# main.net
KiCad netlist of a schematic drawn in EAGLE
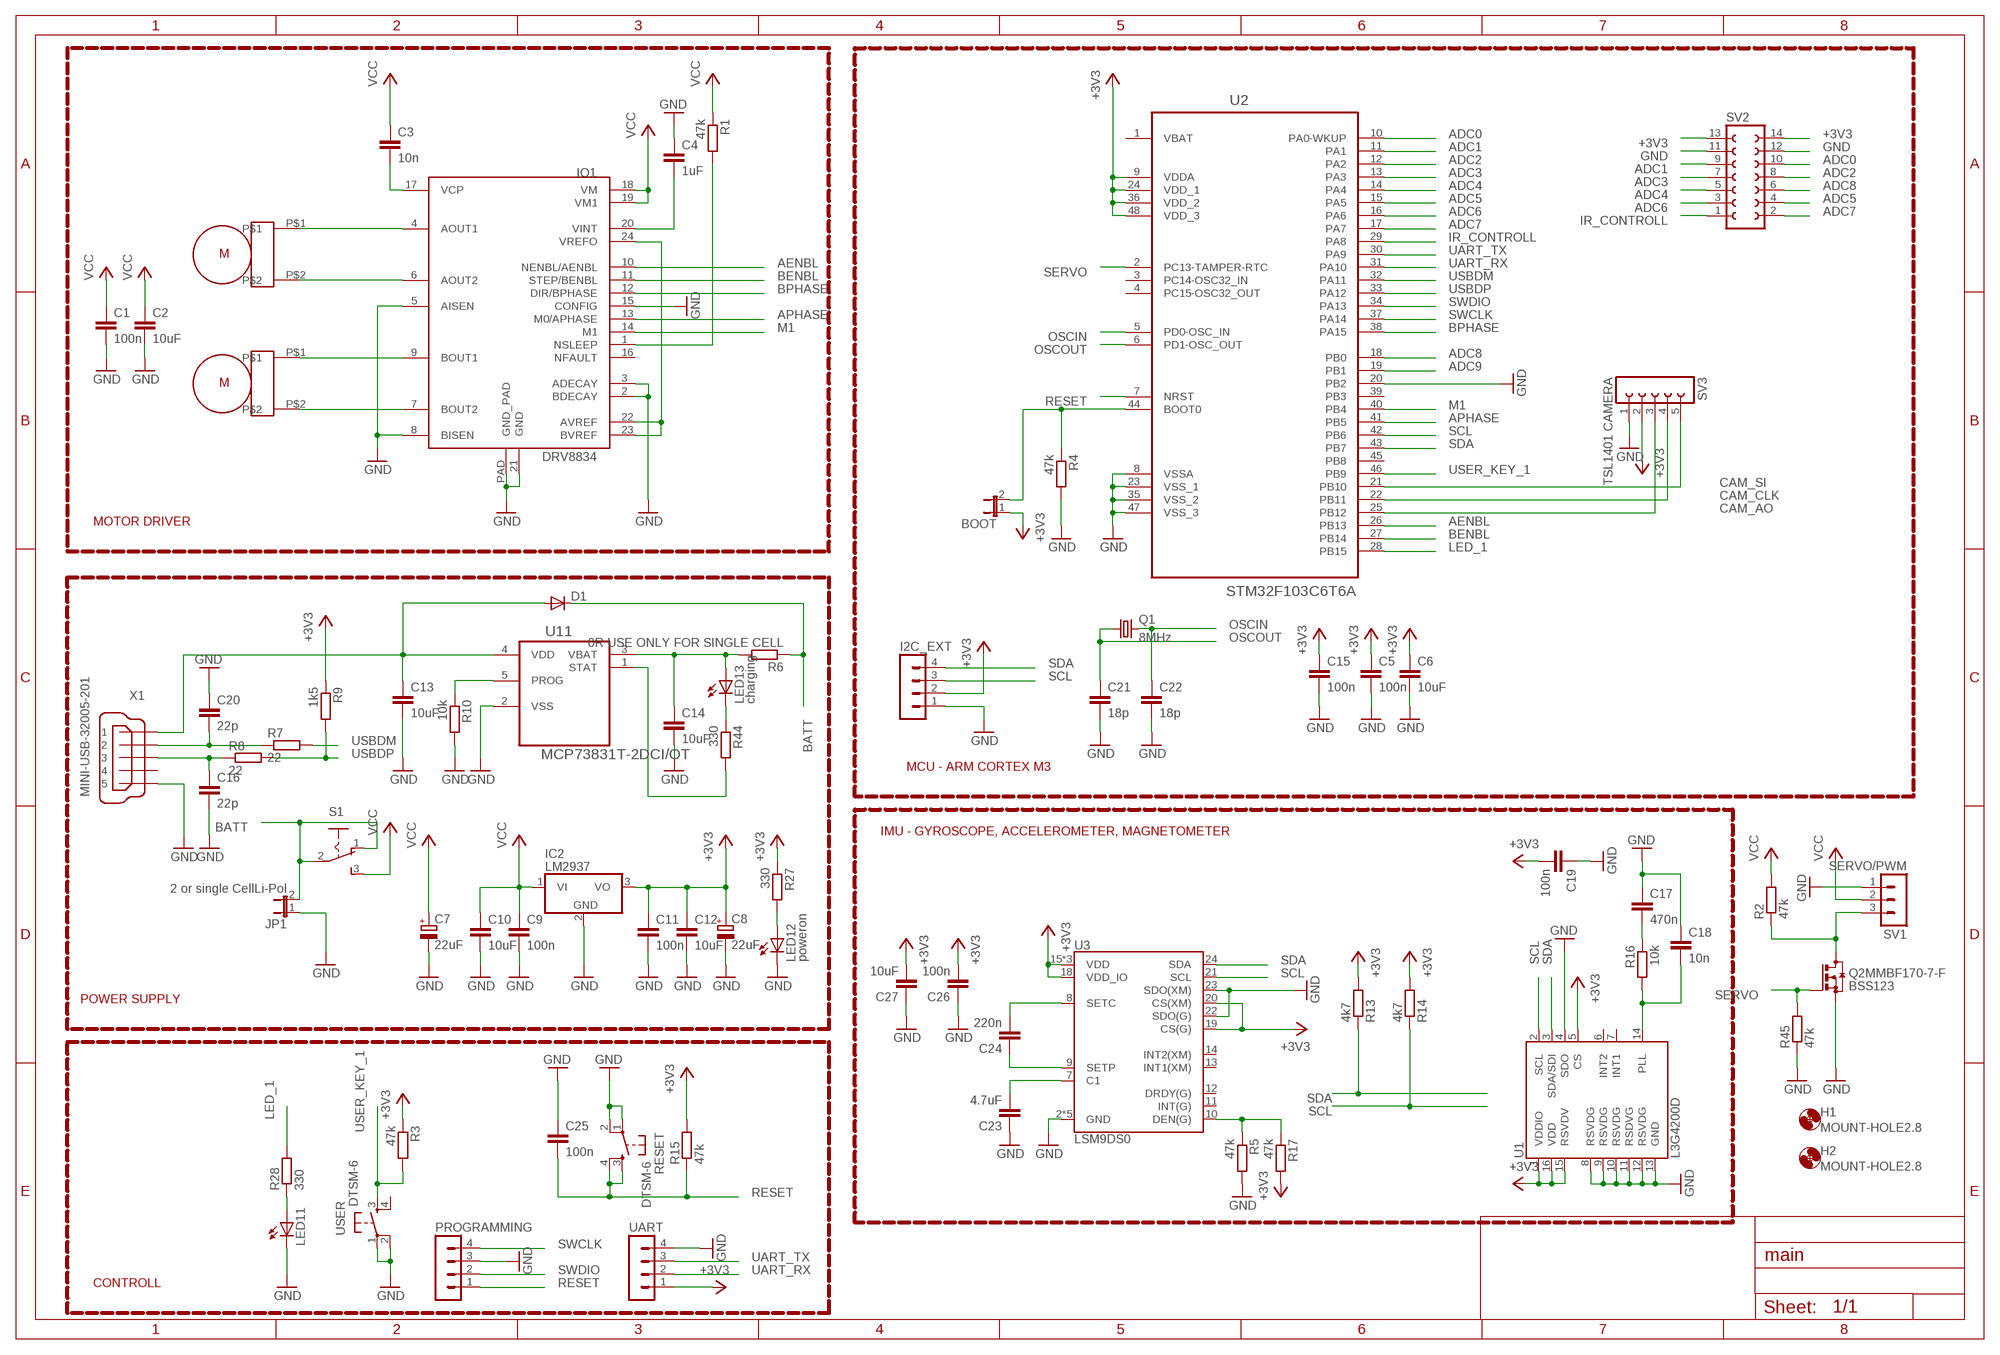
[diagram p0: schematic, sheet 1, part 1 of 2]
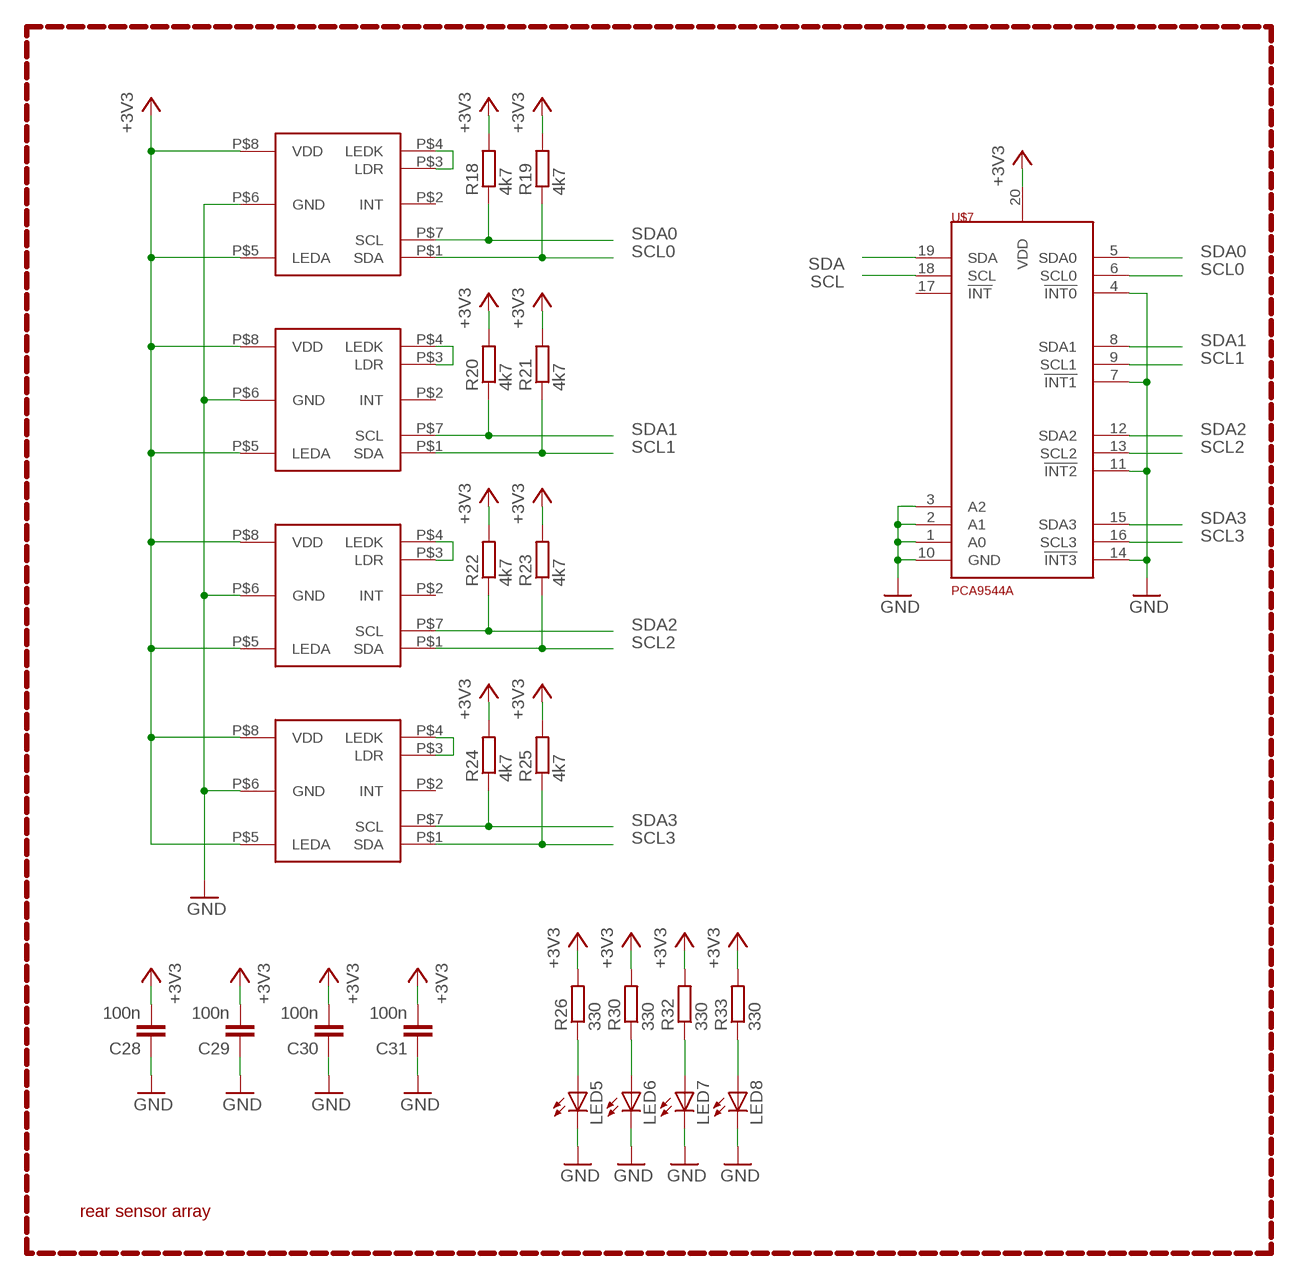
[diagram p1: schematic, sheet 1, part 2 of 2]

(export (version "E")
  (design (tool "Eeschema 10.0.6"))
  (components
    (comp (ref "BOOT")
      (value "JP1E")
      (footprint "eagle-import:JP1")
      (libsource (lib "eagle-import") (part "JP1E"))
    )
    (comp (ref "C1")
      (value "100n")
      (footprint "eagle-import:C1206")
      (libsource (lib "eagle-import") (part "C-EUC1206"))
    )
    (comp (ref "C2")
      (value "10uF")
      (footprint "eagle-import:C1206")
      (libsource (lib "eagle-import") (part "C-EUC1206"))
    )
    (comp (ref "C3")
      (value "10n")
      (footprint "eagle-import:C1206")
      (libsource (lib "eagle-import") (part "C-EUC1206"))
    )
    (comp (ref "C4")
      (value "1uF")
      (footprint "eagle-import:C1206")
      (libsource (lib "eagle-import") (part "C-EUC1206"))
    )
    (comp (ref "C5")
      (value "100n")
      (footprint "eagle-import:C0805")
      (libsource (lib "eagle-import") (part "C-EUC0805"))
    )
    (comp (ref "C6")
      (value "10uF")
      (footprint "eagle-import:C0805")
      (libsource (lib "eagle-import") (part "C-EUC0805"))
    )
    (comp (ref "C7")
      (value "22uF")
      (footprint "eagle-import:153CLV-0505")
      (libsource (lib "eagle-import") (part "CPOL-EU153CLV-0505"))
    )
    (comp (ref "C8")
      (value "22uF")
      (footprint "eagle-import:153CLV-0505")
      (libsource (lib "eagle-import") (part "CPOL-EU153CLV-0505"))
    )
    (comp (ref "C9")
      (value "100n")
      (footprint "eagle-import:C0805")
      (libsource (lib "eagle-import") (part "C-EUC0805"))
    )
    (comp (ref "C10")
      (value "10uF")
      (footprint "eagle-import:C0805")
      (libsource (lib "eagle-import") (part "C-EUC0805"))
    )
    (comp (ref "C11")
      (value "100n")
      (footprint "eagle-import:C0805")
      (libsource (lib "eagle-import") (part "C-EUC0805"))
    )
    (comp (ref "C12")
      (value "10uF")
      (footprint "eagle-import:C0805")
      (libsource (lib "eagle-import") (part "C-EUC0805"))
    )
    (comp (ref "C13")
      (value "10uF")
      (footprint "eagle-import:C0805")
      (libsource (lib "eagle-import") (part "C-EUC0805"))
    )
    (comp (ref "C14")
      (value "10uF")
      (footprint "eagle-import:C0805")
      (libsource (lib "eagle-import") (part "C-EUC0805"))
    )
    (comp (ref "C15")
      (value "100n")
      (footprint "eagle-import:C0805")
      (libsource (lib "eagle-import") (part "C-EUC0805"))
    )
    (comp (ref "C16")
      (value "22p")
      (footprint "eagle-import:C0805")
      (libsource (lib "eagle-import") (part "C-EUC0805"))
    )
    (comp (ref "C17")
      (value "470n")
      (footprint "eagle-import:C0805")
      (libsource (lib "eagle-import") (part "C-EUC0805"))
    )
    (comp (ref "C18")
      (value "10n")
      (footprint "eagle-import:C0805")
      (libsource (lib "eagle-import") (part "C-EUC0805"))
    )
    (comp (ref "C19")
      (value "100n")
      (footprint "eagle-import:C0805")
      (libsource (lib "eagle-import") (part "C-EUC0805"))
    )
    (comp (ref "C20")
      (value "22p")
      (footprint "eagle-import:C0805")
      (libsource (lib "eagle-import") (part "C-EUC0805"))
    )
    (comp (ref "C21")
      (value "18p")
      (footprint "eagle-import:C0805")
      (libsource (lib "eagle-import") (part "C-EUC0805"))
    )
    (comp (ref "C22")
      (value "18p")
      (footprint "eagle-import:C0805")
      (libsource (lib "eagle-import") (part "C-EUC0805"))
    )
    (comp (ref "C23")
      (value "4.7uF")
      (footprint "eagle-import:C0805")
      (libsource (lib "eagle-import") (part "C-EUC0805"))
    )
    (comp (ref "C24")
      (value "220n")
      (footprint "eagle-import:C0805")
      (libsource (lib "eagle-import") (part "C-EUC0805"))
    )
    (comp (ref "C25")
      (value "100n")
      (footprint "eagle-import:C0805")
      (libsource (lib "eagle-import") (part "C-EUC0805"))
    )
    (comp (ref "C26")
      (value "100n")
      (footprint "eagle-import:C0805")
      (libsource (lib "eagle-import") (part "C-EUC0805"))
    )
    (comp (ref "C27")
      (value "10uF")
      (footprint "eagle-import:C0805")
      (libsource (lib "eagle-import") (part "C-EUC0805"))
    )
    (comp (ref "C28")
      (value "100n")
      (footprint "eagle-import:C0805")
      (libsource (lib "eagle-import") (part "C-EUC0805"))
    )
    (comp (ref "C29")
      (value "100n")
      (footprint "eagle-import:C0805")
      (libsource (lib "eagle-import") (part "C-EUC0805"))
    )
    (comp (ref "C30")
      (value "100n")
      (footprint "eagle-import:C0805")
      (libsource (lib "eagle-import") (part "C-EUC0805"))
    )
    (comp (ref "C31")
      (value "100n")
      (footprint "eagle-import:C0805")
      (libsource (lib "eagle-import") (part "C-EUC0805"))
    )
    (comp (ref "D1")
      (value "DIODE-SMB")
      (footprint "eagle-import:SMB")
      (libsource (lib "eagle-import") (part "DIODE-SMB"))
    )
    (comp (ref "H1")
      (value "MOUNT-HOLE2.8")
      (footprint "eagle-import:2,8")
      (libsource (lib "eagle-import") (part "MOUNT-HOLE2.8"))
    )
    (comp (ref "H2")
      (value "MOUNT-HOLE2.8")
      (footprint "eagle-import:2,8")
      (libsource (lib "eagle-import") (part "MOUNT-HOLE2.8"))
    )
    (comp (ref "I2C_EXT")
      (value "MA04-1")
      (footprint "eagle-import:MA04-1")
      (libsource (lib "eagle-import") (part "MA04-1"))
    )
    (comp (ref "IC2")
      (value "LM2937")
      (footprint "eagle-import:TO263-3")
      (libsource (lib "eagle-import") (part "LM2937"))
    )
    (comp (ref "IO1")
      (value "DRV8834")
      (footprint "eagle-import:DRV8834_PCK")
      (libsource (lib "eagle-import") (part "DRV8834"))
    )
    (comp (ref "JP1")
      (value "2 or single CellLi-Pol")
      (footprint "eagle-import:JP1")
      (libsource (lib "eagle-import") (part "JP1E"))
    )
    (comp (ref "LED5")
      (value "LEDCHIPLED_1206")
      (footprint "eagle-import:CHIPLED_1206")
      (libsource (lib "eagle-import") (part "LEDCHIPLED_1206"))
    )
    (comp (ref "LED6")
      (value "LEDCHIPLED_1206")
      (footprint "eagle-import:CHIPLED_1206")
      (libsource (lib "eagle-import") (part "LEDCHIPLED_1206"))
    )
    (comp (ref "LED7")
      (value "LEDCHIPLED_1206")
      (footprint "eagle-import:CHIPLED_1206")
      (libsource (lib "eagle-import") (part "LEDCHIPLED_1206"))
    )
    (comp (ref "LED8")
      (value "LEDCHIPLED_1206")
      (footprint "eagle-import:CHIPLED_1206")
      (libsource (lib "eagle-import") (part "LEDCHIPLED_1206"))
    )
    (comp (ref "LED11")
      (value "LEDCHIPLED_1206")
      (footprint "eagle-import:CHIPLED_1206")
      (libsource (lib "eagle-import") (part "LEDCHIPLED_1206"))
    )
    (comp (ref "LED12")
      (value "poweron")
      (footprint "eagle-import:CHIPLED_1206")
      (libsource (lib "eagle-import") (part "LEDCHIPLED_1206"))
    )
    (comp (ref "LED13")
      (value "charging")
      (footprint "eagle-import:CHIPLED_1206")
      (libsource (lib "eagle-import") (part "LEDCHIPLED_1206"))
    )
    (comp (ref "PROGRAMMING")
      (value "MA04-1")
      (footprint "eagle-import:MA04-1")
      (libsource (lib "eagle-import") (part "MA04-1"))
    )
    (comp (ref "Q1")
      (value "8MHz")
      (footprint "eagle-import:CTS406")
      (libsource (lib "eagle-import") (part "CRYSTALCTS406"))
    )
    (comp (ref "Q2MMBF170-7-F")
      (value "BSS123")
      (footprint "eagle-import:SOT23")
      (libsource (lib "eagle-import") (part "BSS123"))
    )
    (comp (ref "R1")
      (value "47k")
      (footprint "eagle-import:M1206")
      (libsource (lib "eagle-import") (part "R-EU_M1206"))
    )
    (comp (ref "R2")
      (value "47k")
      (footprint "eagle-import:M0805")
      (libsource (lib "eagle-import") (part "R-EU_M0805"))
    )
    (comp (ref "R3")
      (value "47k")
      (footprint "eagle-import:M0805")
      (libsource (lib "eagle-import") (part "R-EU_M0805"))
    )
    (comp (ref "R4")
      (value "47k")
      (footprint "eagle-import:M0805")
      (libsource (lib "eagle-import") (part "R-EU_M0805"))
    )
    (comp (ref "R5")
      (value "47k")
      (footprint "eagle-import:M0805")
      (libsource (lib "eagle-import") (part "R-EU_M0805"))
    )
    (comp (ref "R6")
      (value "0R USE ONLY FOR SINGLE CELL")
      (footprint "eagle-import:M1206")
      (libsource (lib "eagle-import") (part "R-EU_M1206"))
    )
    (comp (ref "R7")
      (value "22")
      (footprint "eagle-import:M0805")
      (libsource (lib "eagle-import") (part "R-EU_M0805"))
    )
    (comp (ref "R8")
      (value "22")
      (footprint "eagle-import:M0805")
      (libsource (lib "eagle-import") (part "R-EU_M0805"))
    )
    (comp (ref "R9")
      (value "1k5")
      (footprint "eagle-import:M0805")
      (libsource (lib "eagle-import") (part "R-EU_M0805"))
    )
    (comp (ref "R10")
      (value "10k")
      (footprint "eagle-import:M0805")
      (libsource (lib "eagle-import") (part "R-EU_M0805"))
    )
    (comp (ref "R13")
      (value "4k7")
      (footprint "eagle-import:M0805")
      (libsource (lib "eagle-import") (part "R-EU_M0805"))
    )
    (comp (ref "R14")
      (value "4k7")
      (footprint "eagle-import:M0805")
      (libsource (lib "eagle-import") (part "R-EU_M0805"))
    )
    (comp (ref "R15")
      (value "47k")
      (footprint "eagle-import:M0805")
      (libsource (lib "eagle-import") (part "R-EU_M0805"))
    )
    (comp (ref "R16")
      (value "10k")
      (footprint "eagle-import:M0805")
      (libsource (lib "eagle-import") (part "R-EU_M0805"))
    )
    (comp (ref "R17")
      (value "47k")
      (footprint "eagle-import:M0805")
      (libsource (lib "eagle-import") (part "R-EU_M0805"))
    )
    (comp (ref "R18")
      (value "4k7")
      (footprint "eagle-import:M0805")
      (libsource (lib "eagle-import") (part "R-EU_M0805"))
    )
    (comp (ref "R19")
      (value "4k7")
      (footprint "eagle-import:M0805")
      (libsource (lib "eagle-import") (part "R-EU_M0805"))
    )
    (comp (ref "R20")
      (value "4k7")
      (footprint "eagle-import:M0805")
      (libsource (lib "eagle-import") (part "R-EU_M0805"))
    )
    (comp (ref "R21")
      (value "4k7")
      (footprint "eagle-import:M0805")
      (libsource (lib "eagle-import") (part "R-EU_M0805"))
    )
    (comp (ref "R22")
      (value "4k7")
      (footprint "eagle-import:M0805")
      (libsource (lib "eagle-import") (part "R-EU_M0805"))
    )
    (comp (ref "R23")
      (value "4k7")
      (footprint "eagle-import:M0805")
      (libsource (lib "eagle-import") (part "R-EU_M0805"))
    )
    (comp (ref "R24")
      (value "4k7")
      (footprint "eagle-import:M0805")
      (libsource (lib "eagle-import") (part "R-EU_M0805"))
    )
    (comp (ref "R25")
      (value "4k7")
      (footprint "eagle-import:M0805")
      (libsource (lib "eagle-import") (part "R-EU_M0805"))
    )
    (comp (ref "R26")
      (value "330")
      (footprint "eagle-import:M0805")
      (libsource (lib "eagle-import") (part "R-EU_M0805"))
    )
    (comp (ref "R27")
      (value "330")
      (footprint "eagle-import:M0805")
      (libsource (lib "eagle-import") (part "R-EU_M0805"))
    )
    (comp (ref "R28")
      (value "330")
      (footprint "eagle-import:M0805")
      (libsource (lib "eagle-import") (part "R-EU_M0805"))
    )
    (comp (ref "R30")
      (value "330")
      (footprint "eagle-import:M0805")
      (libsource (lib "eagle-import") (part "R-EU_M0805"))
    )
    (comp (ref "R32")
      (value "330")
      (footprint "eagle-import:M0805")
      (libsource (lib "eagle-import") (part "R-EU_M0805"))
    )
    (comp (ref "R33")
      (value "330")
      (footprint "eagle-import:M0805")
      (libsource (lib "eagle-import") (part "R-EU_M0805"))
    )
    (comp (ref "R44")
      (value "330")
      (footprint "eagle-import:M0805")
      (libsource (lib "eagle-import") (part "R-EU_M0805"))
    )
    (comp (ref "R45")
      (value "47k")
      (footprint "eagle-import:M0805")
      (libsource (lib "eagle-import") (part "R-EU_M0805"))
    )
    (comp (ref "RESET")
      (value "DTSM-6")
      (footprint "eagle-import:DTSM-6")
      (libsource (lib "eagle-import") (part "DTSM-6"))
    )
    (comp (ref "S1")
      (value "255SB")
      (footprint "eagle-import:255SB")
      (libsource (lib "eagle-import") (part "255SB"))
    )
    (comp (ref "SV1")
      (value "SERVO/PWM")
      (footprint "eagle-import:MA03-1")
      (libsource (lib "eagle-import") (part "MA03-1"))
    )
    (comp (ref "SV2")
      (value "FE07-2")
      (footprint "eagle-import:FE07-2")
      (libsource (lib "eagle-import") (part "FE07-2"))
    )
    (comp (ref "SV3")
      (value "TSL1401 CAMERA")
      (footprint "eagle-import:FE05-1")
      (libsource (lib "eagle-import") (part "FE05-1"))
    )
    (comp (ref "U$1")
      (value "MICRO_METAL_GEAR_MOTOR")
      (footprint "eagle-import:MICRO_METAL_GEAR_MOTOR")
      (libsource (lib "eagle-import") (part "MICRO_METAL_GEAR_MOTOR"))
    )
    (comp (ref "U$2")
      (value "MICRO_METAL_GEAR_MOTOR")
      (footprint "eagle-import:MICRO_METAL_GEAR_MOTOR")
      (libsource (lib "eagle-import") (part "MICRO_METAL_GEAR_MOTOR"))
    )
    (comp (ref "U$3")
      (value "APDS9950")
      (footprint "eagle-import:APDS9950")
      (libsource (lib "eagle-import") (part "APDS9950"))
    )
    (comp (ref "U$4")
      (value "APDS9950")
      (footprint "eagle-import:APDS9950")
      (libsource (lib "eagle-import") (part "APDS9950"))
    )
    (comp (ref "U$5")
      (value "APDS9950")
      (footprint "eagle-import:APDS9950")
      (libsource (lib "eagle-import") (part "APDS9950"))
    )
    (comp (ref "U$6")
      (value "APDS9950")
      (footprint "eagle-import:APDS9950")
      (libsource (lib "eagle-import") (part "APDS9950"))
    )
    (comp (ref "U$7")
      (value "DSSCIRCUITS_PCA9544A")
      (footprint "eagle-import:DSSCIRCUITS_TSSOP20")
      (libsource (lib "eagle-import") (part "DSSCIRCUITS_PCA9544A"))
    )
    (comp (ref "U1")
      (value "L3G4200D")
      (footprint "eagle-import:LGA16-4X4")
      (libsource (lib "eagle-import") (part "L3G4200D"))
    )
    (comp (ref "U2")
      (value "STM32F103C6T6A")
      (footprint "eagle-import:QFP50P900X900X160-48N")
      (libsource (lib "eagle-import") (part "STM32F103C6T6A"))
    )
    (comp (ref "U3")
      (value "LSM9DS0")
      (footprint "eagle-import:LGA-24")
      (libsource (lib "eagle-import") (part "LSM9DS0"))
    )
    (comp (ref "U11")
      (value "MCP73831T-2DCI/OT")
      (footprint "eagle-import:SOT95P270X145-5N")
      (libsource (lib "eagle-import") (part "MCP73831T-2DCI/OT"))
    )
    (comp (ref "UART")
      (value "MA04-1")
      (footprint "eagle-import:MA04-1")
      (libsource (lib "eagle-import") (part "MA04-1"))
    )
    (comp (ref "USER")
      (value "DTSM-6")
      (footprint "eagle-import:DTSM-6")
      (libsource (lib "eagle-import") (part "DTSM-6"))
    )
    (comp (ref "X1")
      (value "MINI-USB-32005-201")
      (footprint "eagle-import:32005-201")
      (libsource (lib "eagle-import") (part "MINI-USB-32005-201"))
    )
  )
  (nets
    (net (code "1") (name "+3V3") (class "Default")
      (node (ref "BOOT") (pin "1") (pinfunction "1_1") (pintype "passive"))
      (node (ref "C11") (pin "1") (pinfunction "1_1") (pintype "passive"))
      (node (ref "C12") (pin "1") (pinfunction "1_1") (pintype "passive"))
      (node (ref "C15") (pin "1") (pinfunction "1_1") (pintype "passive"))
      (node (ref "C19") (pin "2") (pinfunction "2_2") (pintype "passive"))
      (node (ref "C26") (pin "2") (pinfunction "2_2") (pintype "passive"))
      (node (ref "C27") (pin "2") (pinfunction "2_2") (pintype "passive"))
      (node (ref "C28") (pin "2") (pinfunction "2_2") (pintype "passive"))
      (node (ref "C29") (pin "2") (pinfunction "2_2") (pintype "passive"))
      (node (ref "C30") (pin "2") (pinfunction "2_2") (pintype "passive"))
      (node (ref "C31") (pin "2") (pinfunction "2_2") (pintype "passive"))
      (node (ref "C5") (pin "1") (pinfunction "1_1") (pintype "passive"))
      (node (ref "C6") (pin "1") (pinfunction "1_1") (pintype "passive"))
      (node (ref "C8") (pin "+") (pinfunction "+_+") (pintype "passive"))
      (node (ref "I2C_EXT") (pin "2") (pinfunction "2_2") (pintype "passive"))
      (node (ref "IC2") (pin "3") (pinfunction "VO_3") (pintype "passive"))
      (node (ref "R13") (pin "2") (pinfunction "2_2") (pintype "passive"))
      (node (ref "R14") (pin "2") (pinfunction "2_2") (pintype "passive"))
      (node (ref "R15") (pin "2") (pinfunction "2_2") (pintype "passive"))
      (node (ref "R17") (pin "2") (pinfunction "2_2") (pintype "passive"))
      (node (ref "R18") (pin "2") (pinfunction "2_2") (pintype "passive"))
      (node (ref "R19") (pin "2") (pinfunction "2_2") (pintype "passive"))
      (node (ref "R20") (pin "2") (pinfunction "2_2") (pintype "passive"))
      (node (ref "R21") (pin "2") (pinfunction "2_2") (pintype "passive"))
      (node (ref "R22") (pin "2") (pinfunction "2_2") (pintype "passive"))
      (node (ref "R23") (pin "2") (pinfunction "2_2") (pintype "passive"))
      (node (ref "R24") (pin "2") (pinfunction "2_2") (pintype "passive"))
      (node (ref "R25") (pin "2") (pinfunction "2_2") (pintype "passive"))
      (node (ref "R26") (pin "2") (pinfunction "2_2") (pintype "passive"))
      (node (ref "R27") (pin "1") (pinfunction "1_1") (pintype "passive"))
      (node (ref "R3") (pin "1") (pinfunction "1_1") (pintype "passive"))
      (node (ref "R30") (pin "2") (pinfunction "2_2") (pintype "passive"))
      (node (ref "R32") (pin "2") (pinfunction "2_2") (pintype "passive"))
      (node (ref "R33") (pin "2") (pinfunction "2_2") (pintype "passive"))
      (node (ref "R9") (pin "1") (pinfunction "1_1") (pintype "passive"))
      (node (ref "SV2") (pin "13") (pinfunction "13_13") (pintype "passive"))
      (node (ref "SV2") (pin "14") (pinfunction "14_14") (pintype "passive"))
      (node (ref "SV3") (pin "2") (pinfunction "2_2") (pintype "passive"))
      (node (ref "U$3") (pin "P$5") (pinfunction "LEDA_P$5") (pintype "bidirectional"))
      (node (ref "U$3") (pin "P$8") (pinfunction "VDD_P$8") (pintype "bidirectional"))
      (node (ref "U$4") (pin "P$5") (pinfunction "LEDA_P$5") (pintype "bidirectional"))
      (node (ref "U$4") (pin "P$8") (pinfunction "VDD_P$8") (pintype "bidirectional"))
      (node (ref "U$5") (pin "P$5") (pinfunction "LEDA_P$5") (pintype "bidirectional"))
      (node (ref "U$5") (pin "P$8") (pinfunction "VDD_P$8") (pintype "bidirectional"))
      (node (ref "U$6") (pin "P$5") (pinfunction "LEDA_P$5") (pintype "bidirectional"))
      (node (ref "U$6") (pin "P$8") (pinfunction "VDD_P$8") (pintype "bidirectional"))
      (node (ref "U$7") (pin "20") (pinfunction "VDD_20") (pintype "power_in"))
      (node (ref "U1") (pin "1") (pinfunction "VDDIO_1") (pintype "bidirectional"))
      (node (ref "U1") (pin "15") (pinfunction "RSVDV_15") (pintype "bidirectional"))
      (node (ref "U1") (pin "16") (pinfunction "VDD_16") (pintype "bidirectional"))
      (node (ref "U1") (pin "5") (pinfunction "CS_5") (pintype "bidirectional"))
      (node (ref "U2") (pin "24") (pinfunction "VDD_1_24") (pintype "power_in"))
      (node (ref "U2") (pin "36") (pinfunction "VDD_2_36") (pintype "power_in"))
      (node (ref "U2") (pin "48") (pinfunction "VDD_3_48") (pintype "power_in"))
      (node (ref "U2") (pin "9") (pinfunction "VDDA_9") (pintype "power_in"))
      (node (ref "U3") (pin "15") (pinfunction "VDD_15") (pintype "bidirectional"))
      (node (ref "U3") (pin "16") (pinfunction "VDD_16") (pintype "bidirectional"))
      (node (ref "U3") (pin "17") (pinfunction "VDD_17") (pintype "bidirectional"))
      (node (ref "U3") (pin "18") (pinfunction "VDD_IO_18") (pintype "bidirectional"))
      (node (ref "U3") (pin "19") (pinfunction "CS(G)_19") (pintype "bidirectional"))
      (node (ref "U3") (pin "20") (pinfunction "CS(XM)_20") (pintype "bidirectional"))
      (node (ref "UART") (pin "1") (pinfunction "1_1") (pintype "passive"))
    )
    (net (code "2") (name "/ADC0") (class "Default")
      (node (ref "SV2") (pin "10") (pinfunction "10_10") (pintype "passive"))
      (node (ref "U2") (pin "10") (pinfunction "PA0-WKUP_10") (pintype "bidirectional"))
    )
    (net (code "3") (name "/ADC1") (class "Default")
      (node (ref "SV2") (pin "9") (pinfunction "9_9") (pintype "passive"))
      (node (ref "U2") (pin "11") (pinfunction "PA1_11") (pintype "bidirectional"))
    )
    (net (code "4") (name "/ADC2") (class "Default")
      (node (ref "SV2") (pin "8") (pinfunction "8_8") (pintype "passive"))
      (node (ref "U2") (pin "12") (pinfunction "PA2_12") (pintype "bidirectional"))
    )
    (net (code "5") (name "/ADC3") (class "Default")
      (node (ref "SV2") (pin "7") (pinfunction "7_7") (pintype "passive"))
      (node (ref "U2") (pin "13") (pinfunction "PA3_13") (pintype "bidirectional"))
    )
    (net (code "6") (name "/ADC4") (class "Default")
      (node (ref "SV2") (pin "5") (pinfunction "5_5") (pintype "passive"))
      (node (ref "U2") (pin "14") (pinfunction "PA4_14") (pintype "bidirectional"))
    )
    (net (code "7") (name "/ADC5") (class "Default")
      (node (ref "SV2") (pin "4") (pinfunction "4_4") (pintype "passive"))
      (node (ref "U2") (pin "15") (pinfunction "PA5_15") (pintype "bidirectional"))
    )
    (net (code "8") (name "/ADC6") (class "Default")
      (node (ref "SV2") (pin "3") (pinfunction "3_3") (pintype "passive"))
      (node (ref "U2") (pin "16") (pinfunction "PA6_16") (pintype "bidirectional"))
    )
    (net (code "9") (name "/ADC7") (class "Default")
      (node (ref "SV2") (pin "2") (pinfunction "2_2") (pintype "passive"))
      (node (ref "U2") (pin "17") (pinfunction "PA7_17") (pintype "bidirectional"))
    )
    (net (code "10") (name "/ADC8") (class "Default")
      (node (ref "SV2") (pin "6") (pinfunction "6_6") (pintype "passive"))
      (node (ref "U2") (pin "18") (pinfunction "PB0_18") (pintype "bidirectional"))
    )
    (net (code "11") (name "/ADC9") (class "Default")
      (node (ref "U2") (pin "19") (pinfunction "PB1_19") (pintype "bidirectional"))
    )
    (net (code "12") (name "/AENBL") (class "Default")
      (node (ref "IO1") (pin "10") (pinfunction "NENBL/AENBL_10") (pintype "bidirectional"))
      (node (ref "U2") (pin "26") (pinfunction "PB13_26") (pintype "bidirectional"))
    )
    (net (code "13") (name "/APHASE") (class "Default")
      (node (ref "IO1") (pin "13") (pinfunction "M0/APHASE_13") (pintype "bidirectional"))
      (node (ref "U2") (pin "41") (pinfunction "PB5_41") (pintype "bidirectional"))
    )
    (net (code "14") (name "/BATT") (class "Default")
      (node (ref "D1") (pin "C") (pinfunction "C_C") (pintype "passive"))
      (node (ref "JP1") (pin "2") (pinfunction "2_2") (pintype "passive"))
      (node (ref "R6") (pin "1") (pinfunction "1_1") (pintype "passive"))
      (node (ref "S1") (pin "1") (pinfunction "O_1") (pintype "passive"))
      (node (ref "S1") (pin "2") (pinfunction "P_2") (pintype "passive"))
    )
    (net (code "15") (name "/BENBL") (class "Default")
      (node (ref "IO1") (pin "11") (pinfunction "STEP/BENBL_11") (pintype "bidirectional"))
      (node (ref "U2") (pin "27") (pinfunction "PB14_27") (pintype "bidirectional"))
    )
    (net (code "16") (name "/BPHASE") (class "Default")
      (node (ref "IO1") (pin "12") (pinfunction "DIR/BPHASE_12") (pintype "bidirectional"))
      (node (ref "U2") (pin "38") (pinfunction "PA15_38") (pintype "bidirectional"))
    )
    (net (code "17") (name "/CAM_AO") (class "Default")
      (node (ref "SV3") (pin "3") (pinfunction "3_3") (pintype "passive"))
      (node (ref "U2") (pin "25") (pinfunction "PB12_25") (pintype "bidirectional"))
    )
    (net (code "18") (name "/CAM_CLK") (class "Default")
      (node (ref "SV3") (pin "4") (pinfunction "4_4") (pintype "passive"))
      (node (ref "U2") (pin "22") (pinfunction "PB11_22") (pintype "bidirectional"))
    )
    (net (code "19") (name "/CAM_SI") (class "Default")
      (node (ref "SV3") (pin "5") (pinfunction "5_5") (pintype "passive"))
      (node (ref "U2") (pin "21") (pinfunction "PB10_21") (pintype "bidirectional"))
    )
    (net (code "20") (name "/IR_CONTROLL") (class "Default")
      (node (ref "SV2") (pin "1") (pinfunction "1_1") (pintype "passive"))
      (node (ref "U2") (pin "29") (pinfunction "PA8_29") (pintype "bidirectional"))
    )
    (net (code "21") (name "/LED_1") (class "Default")
      (node (ref "R28") (pin "2") (pinfunction "2_2") (pintype "passive"))
      (node (ref "U2") (pin "28") (pinfunction "PB15_28") (pintype "bidirectional"))
    )
    (net (code "22") (name "/M1") (class "Default")
      (node (ref "IO1") (pin "14") (pinfunction "M1_14") (pintype "bidirectional"))
      (node (ref "U2") (pin "40") (pinfunction "PB4_40") (pintype "bidirectional"))
    )
    (net (code "23") (name "/OSCIN") (class "Default")
      (node (ref "C22") (pin "1") (pinfunction "1_1") (pintype "passive"))
      (node (ref "Q1") (pin "3") (pinfunction "2_3") (pintype "passive"))
      (node (ref "U2") (pin "5") (pinfunction "PD0-OSC_IN_5") (pintype "bidirectional"))
    )
    (net (code "24") (name "/OSCOUT") (class "Default")
      (node (ref "C21") (pin "1") (pinfunction "1_1") (pintype "passive"))
      (node (ref "Q1") (pin "1") (pinfunction "1_1") (pintype "passive"))
      (node (ref "U2") (pin "6") (pinfunction "PD1-OSC_OUT_6") (pintype "bidirectional"))
    )
    (net (code "25") (name "/RESET") (class "Default")
      (node (ref "C25") (pin "2") (pinfunction "2_2") (pintype "passive"))
      (node (ref "PROGRAMMING") (pin "1") (pinfunction "1_1") (pintype "passive"))
      (node (ref "R15") (pin "1") (pinfunction "1_1") (pintype "passive"))
      (node (ref "RESET") (pin "3") (pinfunction "3_3") (pintype "passive"))
      (node (ref "RESET") (pin "4") (pinfunction "4_4") (pintype "passive"))
      (node (ref "U2") (pin "7") (pinfunction "NRST_7") (pintype "bidirectional"))
    )
    (net (code "26") (name "/SCL") (class "Default")
      (node (ref "I2C_EXT") (pin "3") (pinfunction "3_3") (pintype "passive"))
      (node (ref "R14") (pin "1") (pinfunction "1_1") (pintype "passive"))
      (node (ref "U$7") (pin "18") (pinfunction "SCL_18") (pintype "bidirectional"))
      (node (ref "U1") (pin "2") (pinfunction "SCL_2") (pintype "bidirectional"))
      (node (ref "U2") (pin "42") (pinfunction "PB6_42") (pintype "bidirectional"))
      (node (ref "U3") (pin "21") (pinfunction "SCL_21") (pintype "bidirectional"))
    )
    (net (code "27") (name "/SCL0") (class "Default")
      (node (ref "R19") (pin "1") (pinfunction "1_1") (pintype "passive"))
      (node (ref "U$3") (pin "P$1") (pinfunction "SDA_P$1") (pintype "bidirectional"))
      (node (ref "U$7") (pin "6") (pinfunction "SCL0_6") (pintype "bidirectional"))
    )
    (net (code "28") (name "/SCL1") (class "Default")
      (node (ref "R21") (pin "1") (pinfunction "1_1") (pintype "passive"))
      (node (ref "U$4") (pin "P$1") (pinfunction "SDA_P$1") (pintype "bidirectional"))
      (node (ref "U$7") (pin "9") (pinfunction "SCL1_9") (pintype "bidirectional"))
    )
    (net (code "29") (name "/SCL2") (class "Default")
      (node (ref "R23") (pin "1") (pinfunction "1_1") (pintype "passive"))
      (node (ref "U$5") (pin "P$1") (pinfunction "SDA_P$1") (pintype "bidirectional"))
      (node (ref "U$7") (pin "13") (pinfunction "SCL2_13") (pintype "bidirectional"))
    )
    (net (code "30") (name "/SCL3") (class "Default")
      (node (ref "R25") (pin "1") (pinfunction "1_1") (pintype "passive"))
      (node (ref "U$6") (pin "P$1") (pinfunction "SDA_P$1") (pintype "bidirectional"))
      (node (ref "U$7") (pin "16") (pinfunction "SCL3_16") (pintype "bidirectional"))
    )
    (net (code "31") (name "/SDA") (class "Default")
      (node (ref "I2C_EXT") (pin "4") (pinfunction "4_4") (pintype "passive"))
      (node (ref "R13") (pin "1") (pinfunction "1_1") (pintype "passive"))
      (node (ref "U$7") (pin "19") (pinfunction "SDA_19") (pintype "bidirectional"))
      (node (ref "U1") (pin "3") (pinfunction "SDA/SDI_3") (pintype "bidirectional"))
      (node (ref "U2") (pin "43") (pinfunction "PB7_43") (pintype "bidirectional"))
      (node (ref "U3") (pin "24") (pinfunction "SDA_24") (pintype "bidirectional"))
    )
    (net (code "32") (name "/SDA0") (class "Default")
      (node (ref "R18") (pin "1") (pinfunction "1_1") (pintype "passive"))
      (node (ref "U$3") (pin "P$7") (pinfunction "SCL_P$7") (pintype "bidirectional"))
      (node (ref "U$7") (pin "5") (pinfunction "SDA0_5") (pintype "bidirectional"))
    )
    (net (code "33") (name "/SDA1") (class "Default")
      (node (ref "R20") (pin "1") (pinfunction "1_1") (pintype "passive"))
      (node (ref "U$4") (pin "P$7") (pinfunction "SCL_P$7") (pintype "bidirectional"))
      (node (ref "U$7") (pin "8") (pinfunction "SDA1_8") (pintype "bidirectional"))
    )
    (net (code "34") (name "/SDA2") (class "Default")
      (node (ref "R22") (pin "1") (pinfunction "1_1") (pintype "passive"))
      (node (ref "U$5") (pin "P$7") (pinfunction "SCL_P$7") (pintype "bidirectional"))
      (node (ref "U$7") (pin "12") (pinfunction "SDA2_12") (pintype "bidirectional"))
    )
    (net (code "35") (name "/SDA3") (class "Default")
      (node (ref "R24") (pin "1") (pinfunction "1_1") (pintype "passive"))
      (node (ref "U$6") (pin "P$7") (pinfunction "SCL_P$7") (pintype "bidirectional"))
      (node (ref "U$7") (pin "15") (pinfunction "SDA3_15") (pintype "bidirectional"))
    )
    (net (code "36") (name "/SERVO") (class "Default")
      (node (ref "Q2MMBF170-7-F") (pin "1") (pinfunction "G_1") (pintype "passive"))
      (node (ref "R45") (pin "2") (pinfunction "2_2") (pintype "passive"))
      (node (ref "U2") (pin "2") (pinfunction "PC13-TAMPER-RTC_2") (pintype "bidirectional"))
    )
    (net (code "37") (name "/SWCLK") (class "Default")
      (node (ref "PROGRAMMING") (pin "4") (pinfunction "4_4") (pintype "passive"))
      (node (ref "U2") (pin "37") (pinfunction "PA14_37") (pintype "bidirectional"))
    )
    (net (code "38") (name "/SWDIO") (class "Default")
      (node (ref "PROGRAMMING") (pin "2") (pinfunction "2_2") (pintype "passive"))
      (node (ref "U2") (pin "34") (pinfunction "PA13_34") (pintype "bidirectional"))
    )
    (net (code "39") (name "/UART_RX") (class "Default")
      (node (ref "U2") (pin "31") (pinfunction "PA10_31") (pintype "bidirectional"))
      (node (ref "UART") (pin "2") (pinfunction "2_2") (pintype "passive"))
    )
    (net (code "40") (name "/UART_TX") (class "Default")
      (node (ref "U2") (pin "30") (pinfunction "PA9_30") (pintype "bidirectional"))
      (node (ref "UART") (pin "3") (pinfunction "3_3") (pintype "passive"))
    )
    (net (code "41") (name "/USBDM") (class "Default")
      (node (ref "R7") (pin "2") (pinfunction "2_2") (pintype "passive"))
      (node (ref "U2") (pin "32") (pinfunction "PA11_32") (pintype "bidirectional"))
    )
    (net (code "42") (name "/USBDP") (class "Default")
      (node (ref "R8") (pin "2") (pinfunction "2_2") (pintype "passive"))
      (node (ref "R9") (pin "2") (pinfunction "2_2") (pintype "passive"))
      (node (ref "U2") (pin "33") (pinfunction "PA12_33") (pintype "bidirectional"))
    )
    (net (code "43") (name "/USER_KEY_1") (class "Default")
      (node (ref "R3") (pin "2") (pinfunction "2_2") (pintype "passive"))
      (node (ref "U2") (pin "46") (pinfunction "PB9_46") (pintype "bidirectional"))
      (node (ref "USER") (pin "3") (pinfunction "3_3") (pintype "passive"))
    )
    (net (code "44") (name "/VBAT") (class "Default")
      (node (ref "U2") (pin "1") (pinfunction "VBAT_1") (pintype "power_in"))
    )
    (net (code "45") (name "GND") (class "Default")
      (node (ref "C1") (pin "2") (pinfunction "2_2") (pintype "passive"))
      (node (ref "C10") (pin "2") (pinfunction "2_2") (pintype "passive"))
      (node (ref "C11") (pin "2") (pinfunction "2_2") (pintype "passive"))
      (node (ref "C12") (pin "2") (pinfunction "2_2") (pintype "passive"))
      (node (ref "C13") (pin "2") (pinfunction "2_2") (pintype "passive"))
      (node (ref "C14") (pin "2") (pinfunction "2_2") (pintype "passive"))
      (node (ref "C15") (pin "2") (pinfunction "2_2") (pintype "passive"))
      (node (ref "C16") (pin "2") (pinfunction "2_2") (pintype "passive"))
      (node (ref "C17") (pin "1") (pinfunction "1_1") (pintype "passive"))
      (node (ref "C18") (pin "1") (pinfunction "1_1") (pintype "passive"))
      (node (ref "C19") (pin "1") (pinfunction "1_1") (pintype "passive"))
      (node (ref "C2") (pin "2") (pinfunction "2_2") (pintype "passive"))
      (node (ref "C20") (pin "1") (pinfunction "1_1") (pintype "passive"))
      (node (ref "C21") (pin "2") (pinfunction "2_2") (pintype "passive"))
      (node (ref "C22") (pin "2") (pinfunction "2_2") (pintype "passive"))
      (node (ref "C23") (pin "1") (pinfunction "1_1") (pintype "passive"))
      (node (ref "C25") (pin "1") (pinfunction "1_1") (pintype "passive"))
      (node (ref "C26") (pin "1") (pinfunction "1_1") (pintype "passive"))
      (node (ref "C27") (pin "1") (pinfunction "1_1") (pintype "passive"))
      (node (ref "C28") (pin "1") (pinfunction "1_1") (pintype "passive"))
      (node (ref "C29") (pin "1") (pinfunction "1_1") (pintype "passive"))
      (node (ref "C30") (pin "1") (pinfunction "1_1") (pintype "passive"))
      (node (ref "C31") (pin "1") (pinfunction "1_1") (pintype "passive"))
      (node (ref "C4") (pin "1") (pinfunction "1_1") (pintype "passive"))
      (node (ref "C5") (pin "2") (pinfunction "2_2") (pintype "passive"))
      (node (ref "C6") (pin "2") (pinfunction "2_2") (pintype "passive"))
      (node (ref "C7") (pin "-") (pinfunction "-_-") (pintype "passive"))
      (node (ref "C8") (pin "-") (pinfunction "-_-") (pintype "passive"))
      (node (ref "C9") (pin "2") (pinfunction "2_2") (pintype "passive"))
      (node (ref "I2C_EXT") (pin "1") (pinfunction "1_1") (pintype "passive"))
      (node (ref "IC2") (pin "2") (pinfunction "GND_2") (pintype "passive"))
      (node (ref "IO1") (pin "15") (pinfunction "CONFIG_15") (pintype "bidirectional"))
      (node (ref "IO1") (pin "2") (pinfunction "BDECAY_2") (pintype "bidirectional"))
      (node (ref "IO1") (pin "21") (pinfunction "GND_21") (pintype "bidirectional"))
      (node (ref "IO1") (pin "3") (pinfunction "ADECAY_3") (pintype "bidirectional"))
      (node (ref "IO1") (pin "5") (pinfunction "AISEN_5") (pintype "bidirectional"))
      (node (ref "IO1") (pin "8") (pinfunction "BISEN_8") (pintype "bidirectional"))
      (node (ref "IO1") (pin "PAD") (pinfunction "GND_PAD_PAD") (pintype "bidirectional"))
      (node (ref "JP1") (pin "1") (pinfunction "1_1") (pintype "passive"))
      (node (ref "LED11") (pin "C") (pinfunction "C_C") (pintype "passive"))
      (node (ref "LED12") (pin "C") (pinfunction "C_C") (pintype "passive"))
      (node (ref "LED5") (pin "C") (pinfunction "C_C") (pintype "passive"))
      (node (ref "LED6") (pin "C") (pinfunction "C_C") (pintype "passive"))
      (node (ref "LED7") (pin "C") (pinfunction "C_C") (pintype "passive"))
      (node (ref "LED8") (pin "C") (pinfunction "C_C") (pintype "passive"))
      (node (ref "PROGRAMMING") (pin "3") (pinfunction "3_3") (pintype "passive"))
      (node (ref "Q2MMBF170-7-F") (pin "2") (pinfunction "S_2") (pintype "passive"))
      (node (ref "R10") (pin "2") (pinfunction "2_2") (pintype "passive"))
      (node (ref "R4") (pin "2") (pinfunction "2_2") (pintype "passive"))
      (node (ref "R45") (pin "1") (pinfunction "1_1") (pintype "passive"))
      (node (ref "R5") (pin "2") (pinfunction "2_2") (pintype "passive"))
      (node (ref "RESET") (pin "1") (pinfunction "1_1") (pintype "passive"))
      (node (ref "RESET") (pin "2") (pinfunction "2_2") (pintype "passive"))
      (node (ref "SV1") (pin "1") (pinfunction "1_1") (pintype "passive"))
      (node (ref "SV2") (pin "11") (pinfunction "11_11") (pintype "passive"))
      (node (ref "SV2") (pin "12") (pinfunction "12_12") (pintype "passive"))
      (node (ref "SV3") (pin "1") (pinfunction "1_1") (pintype "passive"))
      (node (ref "U$3") (pin "P$6") (pinfunction "GND_P$6") (pintype "bidirectional"))
      (node (ref "U$4") (pin "P$6") (pinfunction "GND_P$6") (pintype "bidirectional"))
      (node (ref "U$5") (pin "P$6") (pinfunction "GND_P$6") (pintype "bidirectional"))
      (node (ref "U$6") (pin "P$6") (pinfunction "GND_P$6") (pintype "bidirectional"))
      (node (ref "U$7") (pin "1") (pinfunction "A0_1") (pintype "input"))
      (node (ref "U$7") (pin "10") (pinfunction "GND_10") (pintype "power_in"))
      (node (ref "U$7") (pin "11") (pinfunction "~{INT2}_11") (pintype "input"))
      (node (ref "U$7") (pin "14") (pinfunction "~{INT3}_14") (pintype "input"))
      (node (ref "U$7") (pin "2") (pinfunction "A1_2") (pintype "input"))
      (node (ref "U$7") (pin "3") (pinfunction "A2_3") (pintype "input"))
      (node (ref "U$7") (pin "4") (pinfunction "~{INT0}_4") (pintype "input"))
      (node (ref "U$7") (pin "7") (pinfunction "~{INT1}_7") (pintype "input"))
      (node (ref "U1") (pin "10") (pinfunction "RSVDG_10") (pintype "bidirectional"))
      (node (ref "U1") (pin "11") (pinfunction "RSDVG_11") (pintype "bidirectional"))
      (node (ref "U1") (pin "12") (pinfunction "RSVDG_12") (pintype "bidirectional"))
      (node (ref "U1") (pin "13") (pinfunction "GND_13") (pintype "bidirectional"))
      (node (ref "U1") (pin "4") (pinfunction "SDO_4") (pintype "bidirectional"))
      (node (ref "U1") (pin "8") (pinfunction "RSVDG_8") (pintype "bidirectional"))
      (node (ref "U1") (pin "9") (pinfunction "RSVDG_9") (pintype "bidirectional"))
      (node (ref "U11") (pin "2") (pinfunction "VSS_2") (pintype "power_in"))
      (node (ref "U2") (pin "20") (pinfunction "PB2_20") (pintype "bidirectional"))
      (node (ref "U2") (pin "23") (pinfunction "VSS_1_23") (pintype "passive"))
      (node (ref "U2") (pin "35") (pinfunction "VSS_2_35") (pintype "passive"))
      (node (ref "U2") (pin "47") (pinfunction "VSS_3_47") (pintype "passive"))
      (node (ref "U2") (pin "8") (pinfunction "VSSA_8") (pintype "passive"))
      (node (ref "U3") (pin "2") (pinfunction "GND_2") (pintype "bidirectional"))
      (node (ref "U3") (pin "22") (pinfunction "SDO(G)_22") (pintype "bidirectional"))
      (node (ref "U3") (pin "23") (pinfunction "SDO(XM)_23") (pintype "bidirectional"))
      (node (ref "U3") (pin "3") (pinfunction "GND_3") (pintype "bidirectional"))
      (node (ref "U3") (pin "4") (pinfunction "GND_4") (pintype "bidirectional"))
      (node (ref "U3") (pin "5") (pinfunction "GND_5") (pintype "bidirectional"))
      (node (ref "U3") (pin "6") (pinfunction "GND_6") (pintype "bidirectional"))
      (node (ref "UART") (pin "4") (pinfunction "4_4") (pintype "passive"))
      (node (ref "USER") (pin "1") (pinfunction "1_1") (pintype "passive"))
      (node (ref "USER") (pin "2") (pinfunction "2_2") (pintype "passive"))
      (node (ref "X1") (pin "5") (pinfunction "5_5") (pintype "passive"))
    )
    (net (code "46") (name "Net-(C16-Pad1)") (class "Default")
      (node (ref "C16") (pin "1") (pinfunction "1_1") (pintype "passive"))
      (node (ref "R8") (pin "1") (pinfunction "1_1") (pintype "passive"))
      (node (ref "X1") (pin "3") (pinfunction "3_3") (pintype "passive"))
    )
    (net (code "47") (name "Net-(C17-Pad2)") (class "Default")
      (node (ref "C17") (pin "2") (pinfunction "2_2") (pintype "passive"))
      (node (ref "R16") (pin "1") (pinfunction "1_1") (pintype "passive"))
    )
    (net (code "48") (name "Net-(C20-Pad2)") (class "Default")
      (node (ref "C20") (pin "2") (pinfunction "2_2") (pintype "passive"))
      (node (ref "R7") (pin "1") (pinfunction "1_1") (pintype "passive"))
      (node (ref "X1") (pin "2") (pinfunction "2_2") (pintype "passive"))
    )
    (net (code "49") (name "Net-(IO1-AOUT1)") (class "Default")
      (node (ref "IO1") (pin "4") (pinfunction "AOUT1_4") (pintype "bidirectional"))
      (node (ref "U$1") (pin "P$1") (pinfunction "P$1_P$1") (pintype "bidirectional"))
    )
    (net (code "50") (name "Net-(IO1-AOUT2)") (class "Default")
      (node (ref "IO1") (pin "6") (pinfunction "AOUT2_6") (pintype "bidirectional"))
      (node (ref "U$1") (pin "P$2") (pinfunction "P$2_P$2") (pintype "bidirectional"))
    )
    (net (code "51") (name "Net-(IO1-AVREF)") (class "Default")
      (node (ref "IO1") (pin "22") (pinfunction "AVREF_22") (pintype "bidirectional"))
      (node (ref "IO1") (pin "23") (pinfunction "BVREF_23") (pintype "bidirectional"))
      (node (ref "IO1") (pin "24") (pinfunction "VREFO_24") (pintype "bidirectional"))
    )
    (net (code "52") (name "Net-(IO1-BOUT1)") (class "Default")
      (node (ref "IO1") (pin "9") (pinfunction "BOUT1_9") (pintype "bidirectional"))
      (node (ref "U$2") (pin "P$1") (pinfunction "P$1_P$1") (pintype "bidirectional"))
    )
    (net (code "53") (name "Net-(IO1-BOUT2)") (class "Default")
      (node (ref "IO1") (pin "7") (pinfunction "BOUT2_7") (pintype "bidirectional"))
      (node (ref "U$2") (pin "P$2") (pinfunction "P$2_P$2") (pintype "bidirectional"))
    )
    (net (code "54") (name "Net-(IO1-NSLEEP)") (class "Default")
      (node (ref "IO1") (pin "1") (pinfunction "NSLEEP_1") (pintype "bidirectional"))
      (node (ref "R1") (pin "2") (pinfunction "2_2") (pintype "passive"))
    )
    (net (code "55") (name "Net-(IO1-VCP)") (class "Default")
      (node (ref "C3") (pin "2") (pinfunction "2_2") (pintype "passive"))
      (node (ref "IO1") (pin "17") (pinfunction "VCP_17") (pintype "bidirectional"))
    )
    (net (code "56") (name "Net-(IO1-VINT)") (class "Default")
      (node (ref "C4") (pin "2") (pinfunction "2_2") (pintype "passive"))
      (node (ref "IO1") (pin "20") (pinfunction "VINT_20") (pintype "bidirectional"))
    )
    (net (code "57") (name "Net-(LED5-PadA)") (class "Default")
      (node (ref "LED5") (pin "A") (pinfunction "A_A") (pintype "passive"))
      (node (ref "R26") (pin "1") (pinfunction "1_1") (pintype "passive"))
    )
    (net (code "58") (name "Net-(LED6-PadA)") (class "Default")
      (node (ref "LED6") (pin "A") (pinfunction "A_A") (pintype "passive"))
      (node (ref "R30") (pin "1") (pinfunction "1_1") (pintype "passive"))
    )
    (net (code "59") (name "Net-(LED7-PadA)") (class "Default")
      (node (ref "LED7") (pin "A") (pinfunction "A_A") (pintype "passive"))
      (node (ref "R32") (pin "1") (pinfunction "1_1") (pintype "passive"))
    )
    (net (code "60") (name "Net-(LED8-PadA)") (class "Default")
      (node (ref "LED8") (pin "A") (pinfunction "A_A") (pintype "passive"))
      (node (ref "R33") (pin "1") (pinfunction "1_1") (pintype "passive"))
    )
    (net (code "61") (name "Net-(LED11-PadA)") (class "Default")
      (node (ref "LED11") (pin "A") (pinfunction "A_A") (pintype "passive"))
      (node (ref "R28") (pin "1") (pinfunction "1_1") (pintype "passive"))
    )
    (net (code "62") (name "Net-(LED12-PadA)") (class "Default")
      (node (ref "LED12") (pin "A") (pinfunction "A_A") (pintype "passive"))
      (node (ref "R27") (pin "2") (pinfunction "2_2") (pintype "passive"))
    )
    (net (code "63") (name "Net-(LED13-PadC)") (class "Default")
      (node (ref "LED13") (pin "C") (pinfunction "C_C") (pintype "passive"))
      (node (ref "R44") (pin "1") (pinfunction "1_1") (pintype "passive"))
    )
    (net (code "64") (name "Net-(Q2MMBF170-7-F-D)") (class "Default")
      (node (ref "Q2MMBF170-7-F") (pin "3") (pinfunction "D_3") (pintype "passive"))
      (node (ref "R2") (pin "1") (pinfunction "1_1") (pintype "passive"))
      (node (ref "SV1") (pin "3") (pinfunction "3_3") (pintype "passive"))
    )
    (net (code "65") (name "Net-(U$3-LDR)") (class "Default")
      (node (ref "U$3") (pin "P$3") (pinfunction "LDR_P$3") (pintype "bidirectional"))
      (node (ref "U$3") (pin "P$4") (pinfunction "LEDK_P$4") (pintype "bidirectional"))
    )
    (net (code "66") (name "Net-(U$4-LDR)") (class "Default")
      (node (ref "U$4") (pin "P$3") (pinfunction "LDR_P$3") (pintype "bidirectional"))
      (node (ref "U$4") (pin "P$4") (pinfunction "LEDK_P$4") (pintype "bidirectional"))
    )
    (net (code "67") (name "Net-(U$5-LDR)") (class "Default")
      (node (ref "U$5") (pin "P$3") (pinfunction "LDR_P$3") (pintype "bidirectional"))
      (node (ref "U$5") (pin "P$4") (pinfunction "LEDK_P$4") (pintype "bidirectional"))
    )
    (net (code "68") (name "Net-(U$6-LDR)") (class "Default")
      (node (ref "U$6") (pin "P$3") (pinfunction "LDR_P$3") (pintype "bidirectional"))
      (node (ref "U$6") (pin "P$4") (pinfunction "LEDK_P$4") (pintype "bidirectional"))
    )
    (net (code "69") (name "Net-(U1-PLL)") (class "Default")
      (node (ref "C18") (pin "2") (pinfunction "2_2") (pintype "passive"))
      (node (ref "R16") (pin "2") (pinfunction "2_2") (pintype "passive"))
      (node (ref "U1") (pin "14") (pinfunction "PLL_14") (pintype "bidirectional"))
    )
    (net (code "70") (name "Net-(U2-BOOT0)") (class "Default")
      (node (ref "BOOT") (pin "2") (pinfunction "2_2") (pintype "passive"))
      (node (ref "R4") (pin "1") (pinfunction "1_1") (pintype "passive"))
      (node (ref "U2") (pin "44") (pinfunction "BOOT0_44") (pintype "input"))
    )
    (net (code "71") (name "Net-(U3-C1)") (class "Default")
      (node (ref "C23") (pin "2") (pinfunction "2_2") (pintype "passive"))
      (node (ref "U3") (pin "7") (pinfunction "C1_7") (pintype "bidirectional"))
    )
    (net (code "72") (name "Net-(U3-DEN(G))") (class "Default")
      (node (ref "R17") (pin "1") (pinfunction "1_1") (pintype "passive"))
      (node (ref "R5") (pin "1") (pinfunction "1_1") (pintype "passive"))
      (node (ref "U3") (pin "10") (pinfunction "DEN(G)_10") (pintype "bidirectional"))
    )
    (net (code "73") (name "Net-(U3-SETC)") (class "Default")
      (node (ref "C24") (pin "2") (pinfunction "2_2") (pintype "passive"))
      (node (ref "U3") (pin "8") (pinfunction "SETC_8") (pintype "bidirectional"))
    )
    (net (code "74") (name "Net-(U3-SETP)") (class "Default")
      (node (ref "C24") (pin "1") (pinfunction "1_1") (pintype "passive"))
      (node (ref "U3") (pin "9") (pinfunction "SETP_9") (pintype "bidirectional"))
    )
    (net (code "75") (name "Net-(U11-PROG)") (class "Default")
      (node (ref "R10") (pin "1") (pinfunction "1_1") (pintype "passive"))
      (node (ref "U11") (pin "5") (pinfunction "PROG_5") (pintype "input"))
    )
    (net (code "76") (name "Net-(U11-STAT)") (class "Default")
      (node (ref "R44") (pin "2") (pinfunction "2_2") (pintype "passive"))
      (node (ref "U11") (pin "1") (pinfunction "STAT_1") (pintype "output"))
    )
    (net (code "77") (name "Net-(U11-VBAT)") (class "Default")
      (node (ref "C14") (pin "1") (pinfunction "1_1") (pintype "passive"))
      (node (ref "LED13") (pin "A") (pinfunction "A_A") (pintype "passive"))
      (node (ref "R6") (pin "2") (pinfunction "2_2") (pintype "passive"))
      (node (ref "U11") (pin "3") (pinfunction "VBAT_3") (pintype "power_in"))
    )
    (net (code "78") (name "Net-(U11-VDD)") (class "Default")
      (node (ref "C13") (pin "1") (pinfunction "1_1") (pintype "passive"))
      (node (ref "D1") (pin "A") (pinfunction "A_A") (pintype "passive"))
      (node (ref "U11") (pin "4") (pinfunction "VDD_4") (pintype "power_in"))
      (node (ref "X1") (pin "1") (pinfunction "1_1") (pintype "passive"))
    )
    (net (code "79") (name "VCC") (class "Default")
      (node (ref "C1") (pin "1") (pinfunction "1_1") (pintype "passive"))
      (node (ref "C10") (pin "1") (pinfunction "1_1") (pintype "passive"))
      (node (ref "C2") (pin "1") (pinfunction "1_1") (pintype "passive"))
      (node (ref "C3") (pin "1") (pinfunction "1_1") (pintype "passive"))
      (node (ref "C7") (pin "+") (pinfunction "+_+") (pintype "passive"))
      (node (ref "C9") (pin "1") (pinfunction "1_1") (pintype "passive"))
      (node (ref "IC2") (pin "1") (pinfunction "VI_1") (pintype "input"))
      (node (ref "IO1") (pin "18") (pinfunction "VM_18") (pintype "bidirectional"))
      (node (ref "IO1") (pin "19") (pinfunction "VM1_19") (pintype "bidirectional"))
      (node (ref "R1") (pin "1") (pinfunction "1_1") (pintype "passive"))
      (node (ref "R2") (pin "2") (pinfunction "2_2") (pintype "passive"))
      (node (ref "S1") (pin "3") (pinfunction "S_3") (pintype "passive"))
      (node (ref "SV1") (pin "2") (pinfunction "2_2") (pintype "passive"))
    )
    (net (code "80") (name "unconnected-(IO1-NFAULT-Pad16)") (class "Default")
      (node (ref "IO1") (pin "16") (pinfunction "NFAULT_16") (pintype "bidirectional"))
    )
    (net (code "81") (name "unconnected-(U$3-INT-PadP$2)") (class "Default")
      (node (ref "U$3") (pin "P$2") (pinfunction "INT_P$2") (pintype "bidirectional"))
    )
    (net (code "82") (name "unconnected-(U$4-INT-PadP$2)") (class "Default")
      (node (ref "U$4") (pin "P$2") (pinfunction "INT_P$2") (pintype "bidirectional"))
    )
    (net (code "83") (name "unconnected-(U$5-INT-PadP$2)") (class "Default")
      (node (ref "U$5") (pin "P$2") (pinfunction "INT_P$2") (pintype "bidirectional"))
    )
    (net (code "84") (name "unconnected-(U$6-INT-PadP$2)") (class "Default")
      (node (ref "U$6") (pin "P$2") (pinfunction "INT_P$2") (pintype "bidirectional"))
    )
    (net (code "85") (name "unconnected-(U$7-~{INT}-Pad17)") (class "Default")
      (node (ref "U$7") (pin "17") (pinfunction "~{INT}_17") (pintype "output"))
    )
    (net (code "86") (name "unconnected-(U1-INT1-Pad7)") (class "Default")
      (node (ref "U1") (pin "7") (pinfunction "INT1_7") (pintype "bidirectional"))
    )
    (net (code "87") (name "unconnected-(U1-INT2-Pad6)") (class "Default")
      (node (ref "U1") (pin "6") (pinfunction "INT2_6") (pintype "bidirectional"))
    )
    (net (code "88") (name "unconnected-(U2-PB3-Pad39)") (class "Default")
      (node (ref "U2") (pin "39") (pinfunction "PB3_39") (pintype "bidirectional"))
    )
    (net (code "89") (name "unconnected-(U2-PB8-Pad45)") (class "Default")
      (node (ref "U2") (pin "45") (pinfunction "PB8_45") (pintype "bidirectional"))
    )
    (net (code "90") (name "unconnected-(U2-PC14-OSC32_IN-Pad3)") (class "Default")
      (node (ref "U2") (pin "3") (pinfunction "PC14-OSC32_IN_3") (pintype "bidirectional"))
    )
    (net (code "91") (name "unconnected-(U2-PC15-OSC32_OUT-Pad4)") (class "Default")
      (node (ref "U2") (pin "4") (pinfunction "PC15-OSC32_OUT_4") (pintype "bidirectional"))
    )
    (net (code "92") (name "unconnected-(U3-DRDY(G)-Pad12)") (class "Default")
      (node (ref "U3") (pin "12") (pinfunction "DRDY(G)_12") (pintype "bidirectional"))
    )
    (net (code "93") (name "unconnected-(U3-INT(G)-Pad11)") (class "Default")
      (node (ref "U3") (pin "11") (pinfunction "INT(G)_11") (pintype "bidirectional"))
    )
    (net (code "94") (name "unconnected-(U3-INT1(XM)-Pad13)") (class "Default")
      (node (ref "U3") (pin "13") (pinfunction "INT1(XM)_13") (pintype "bidirectional"))
    )
    (net (code "95") (name "unconnected-(U3-INT2(XM)-Pad14)") (class "Default")
      (node (ref "U3") (pin "14") (pinfunction "INT2(XM)_14") (pintype "bidirectional"))
    )
    (net (code "96") (name "unconnected-(USER-Pad4)") (class "Default")
      (node (ref "USER") (pin "4") (pinfunction "4_4") (pintype "passive"))
    )
    (net (code "97") (name "unconnected-(X1-Pad4)") (class "Default")
      (node (ref "X1") (pin "4") (pinfunction "4_4") (pintype "passive"))
    )
  )
)
